# WithoutBypassCap.net
KiCad netlist of a schematic drawn in EAGLE
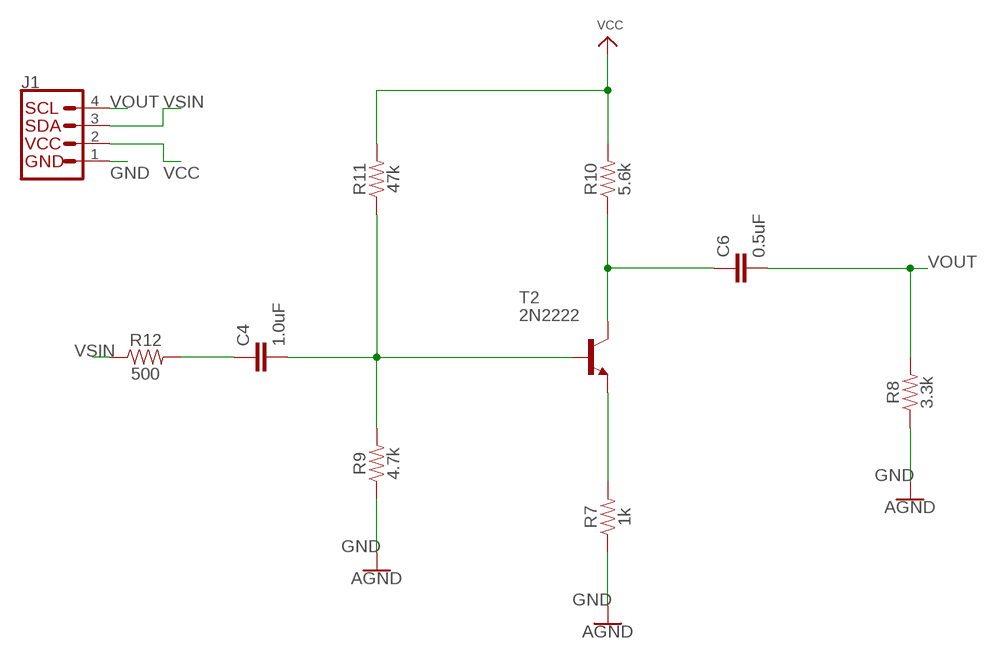
[diagram p0: schematic, sheet 1]

(export (version "E")
  (design (tool "Eeschema 10.0.6"))
  (components
    (comp (ref "C4")
      (value "1.0uF")
      (footprint "eagle-import:0603")
      (libsource (lib "eagle-import") (part "1.0UF-0603-16V-10%"))
    )
    (comp (ref "C6")
      (value "0.5uF")
      (footprint "eagle-import:0603")
      (libsource (lib "eagle-import") (part "1.0UF-0603-16V-10%"))
    )
    (comp (ref "J1")
      (value "QWIIC_CONNECTORJS-1MM")
      (footprint "eagle-import:1X04_1MM_RA")
      (libsource (lib "eagle-import") (part "QWIIC_CONNECTORJS-1MM"))
    )
    (comp (ref "R7")
      (value "1k")
      (footprint "eagle-import:0603")
      (libsource (lib "eagle-import") (part "1KOHM-0603-1/10W-1%"))
    )
    (comp (ref "R8")
      (value "3.3k")
      (footprint "eagle-import:0603")
      (libsource (lib "eagle-import") (part "3.3KOHM-0603-1/10W-1%"))
    )
    (comp (ref "R9")
      (value "4.7k")
      (footprint "eagle-import:0603")
      (libsource (lib "eagle-import") (part "4.7KOHM-0603-1/10W-1%"))
    )
    (comp (ref "R10")
      (value "5.6k")
      (footprint "eagle-import:0603")
      (libsource (lib "eagle-import") (part "5.6KOHM-0603-1/10W-1%"))
    )
    (comp (ref "R11")
      (value "47k")
      (footprint "eagle-import:0603")
      (libsource (lib "eagle-import") (part "47KOHM-0603-1/10W-1%"))
    )
    (comp (ref "R12")
      (value "500")
      (footprint "eagle-import:0603")
      (libsource (lib "eagle-import") (part "300OHM-0603-1/10W-1%"))
    )
    (comp (ref "T2")
      (value "2N2222")
      (footprint "eagle-import:TO92-EBC-OVAL")
      (libsource (lib "eagle-import") (part "2N2222"))
    )
  )
  (nets
    (net (code "1") (name "/VOUT") (class "Default")
      (node (ref "C6") (pin "2") (pinfunction "2_2") (pintype "passive"))
      (node (ref "J1") (pin "4") (pinfunction "SCL_4") (pintype "passive"))
      (node (ref "R8") (pin "2") (pinfunction "2_2") (pintype "passive"))
    )
    (net (code "2") (name "/VSIN") (class "Default")
      (node (ref "J1") (pin "3") (pinfunction "SDA_3") (pintype "passive"))
      (node (ref "R12") (pin "1") (pinfunction "1_1") (pintype "passive"))
    )
    (net (code "3") (name "AGND") (class "Default")
      (node (ref "J1") (pin "1") (pinfunction "GND_1") (pintype "power_in"))
      (node (ref "R7") (pin "1") (pinfunction "1_1") (pintype "passive"))
      (node (ref "R8") (pin "1") (pinfunction "1_1") (pintype "passive"))
      (node (ref "R9") (pin "1") (pinfunction "1_1") (pintype "passive"))
    )
    (net (code "4") (name "Net-(C4-Pad1)") (class "Default")
      (node (ref "C4") (pin "1") (pinfunction "1_1") (pintype "passive"))
      (node (ref "R12") (pin "2") (pinfunction "2_2") (pintype "passive"))
    )
    (net (code "5") (name "Net-(C4-Pad2)") (class "Default")
      (node (ref "C4") (pin "2") (pinfunction "2_2") (pintype "passive"))
      (node (ref "R11") (pin "1") (pinfunction "1_1") (pintype "passive"))
      (node (ref "R9") (pin "2") (pinfunction "2_2") (pintype "passive"))
      (node (ref "T2") (pin "B") (pinfunction "B_B") (pintype "passive"))
    )
    (net (code "6") (name "Net-(C6-Pad1)") (class "Default")
      (node (ref "C6") (pin "1") (pinfunction "1_1") (pintype "passive"))
      (node (ref "R10") (pin "1") (pinfunction "1_1") (pintype "passive"))
      (node (ref "T2") (pin "C") (pinfunction "C_C") (pintype "passive"))
    )
    (net (code "7") (name "Net-(R7-Pad2)") (class "Default")
      (node (ref "R7") (pin "2") (pinfunction "2_2") (pintype "passive"))
      (node (ref "T2") (pin "E") (pinfunction "E_E") (pintype "passive"))
    )
    (net (code "8") (name "VCC") (class "Default")
      (node (ref "J1") (pin "2") (pinfunction "VCC_2") (pintype "power_in"))
      (node (ref "R10") (pin "2") (pinfunction "2_2") (pintype "passive"))
      (node (ref "R11") (pin "2") (pinfunction "2_2") (pintype "passive"))
    )
  )
)
